# braids_v50.net
KiCad netlist of a schematic drawn in EAGLE
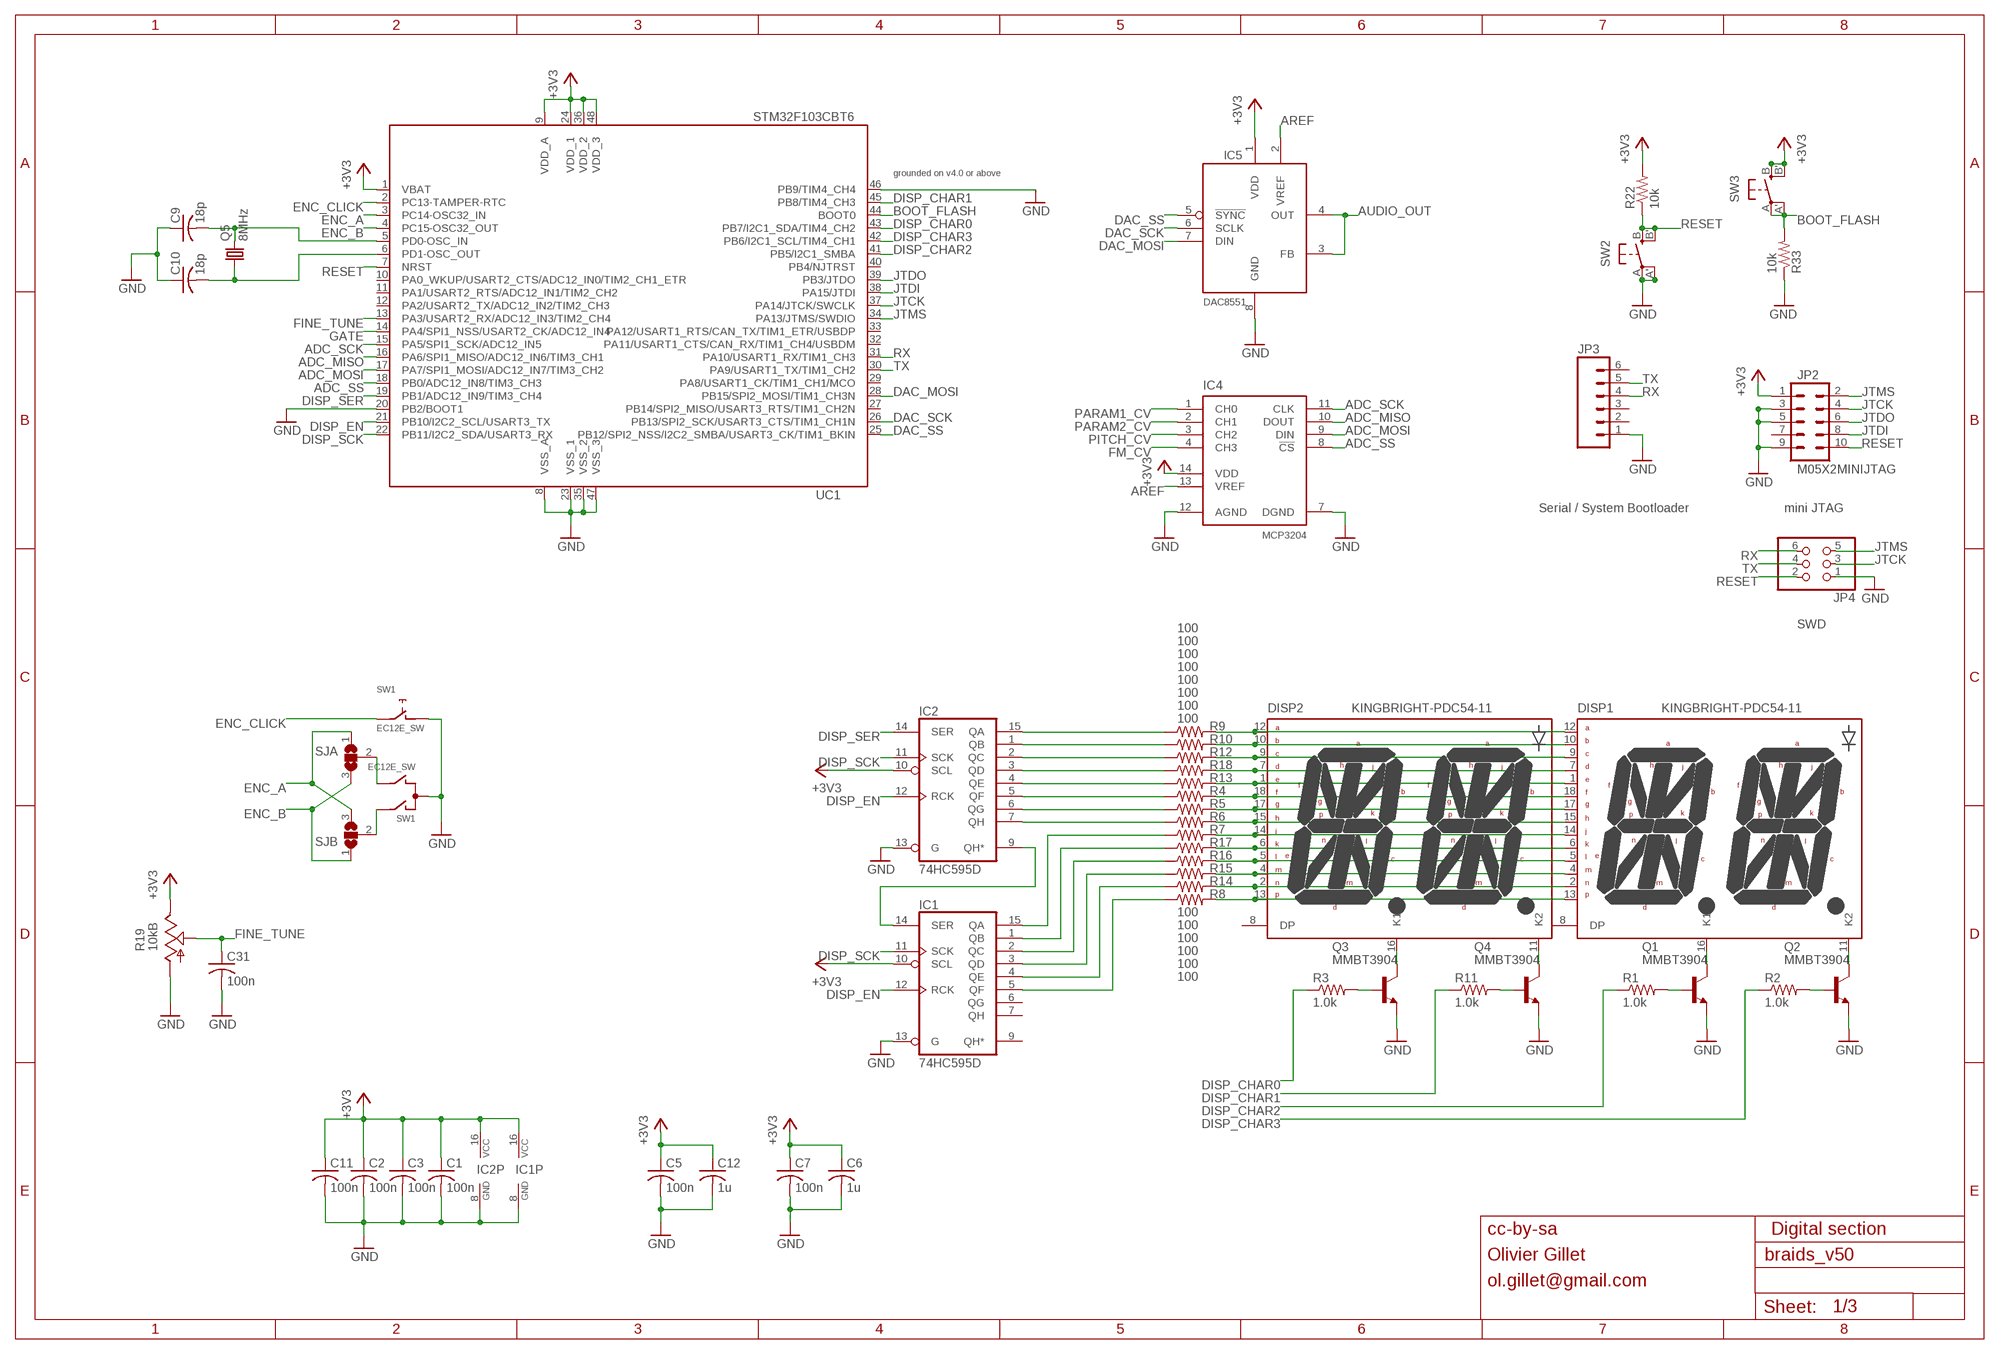
[diagram p0: schematic, sheet 1]
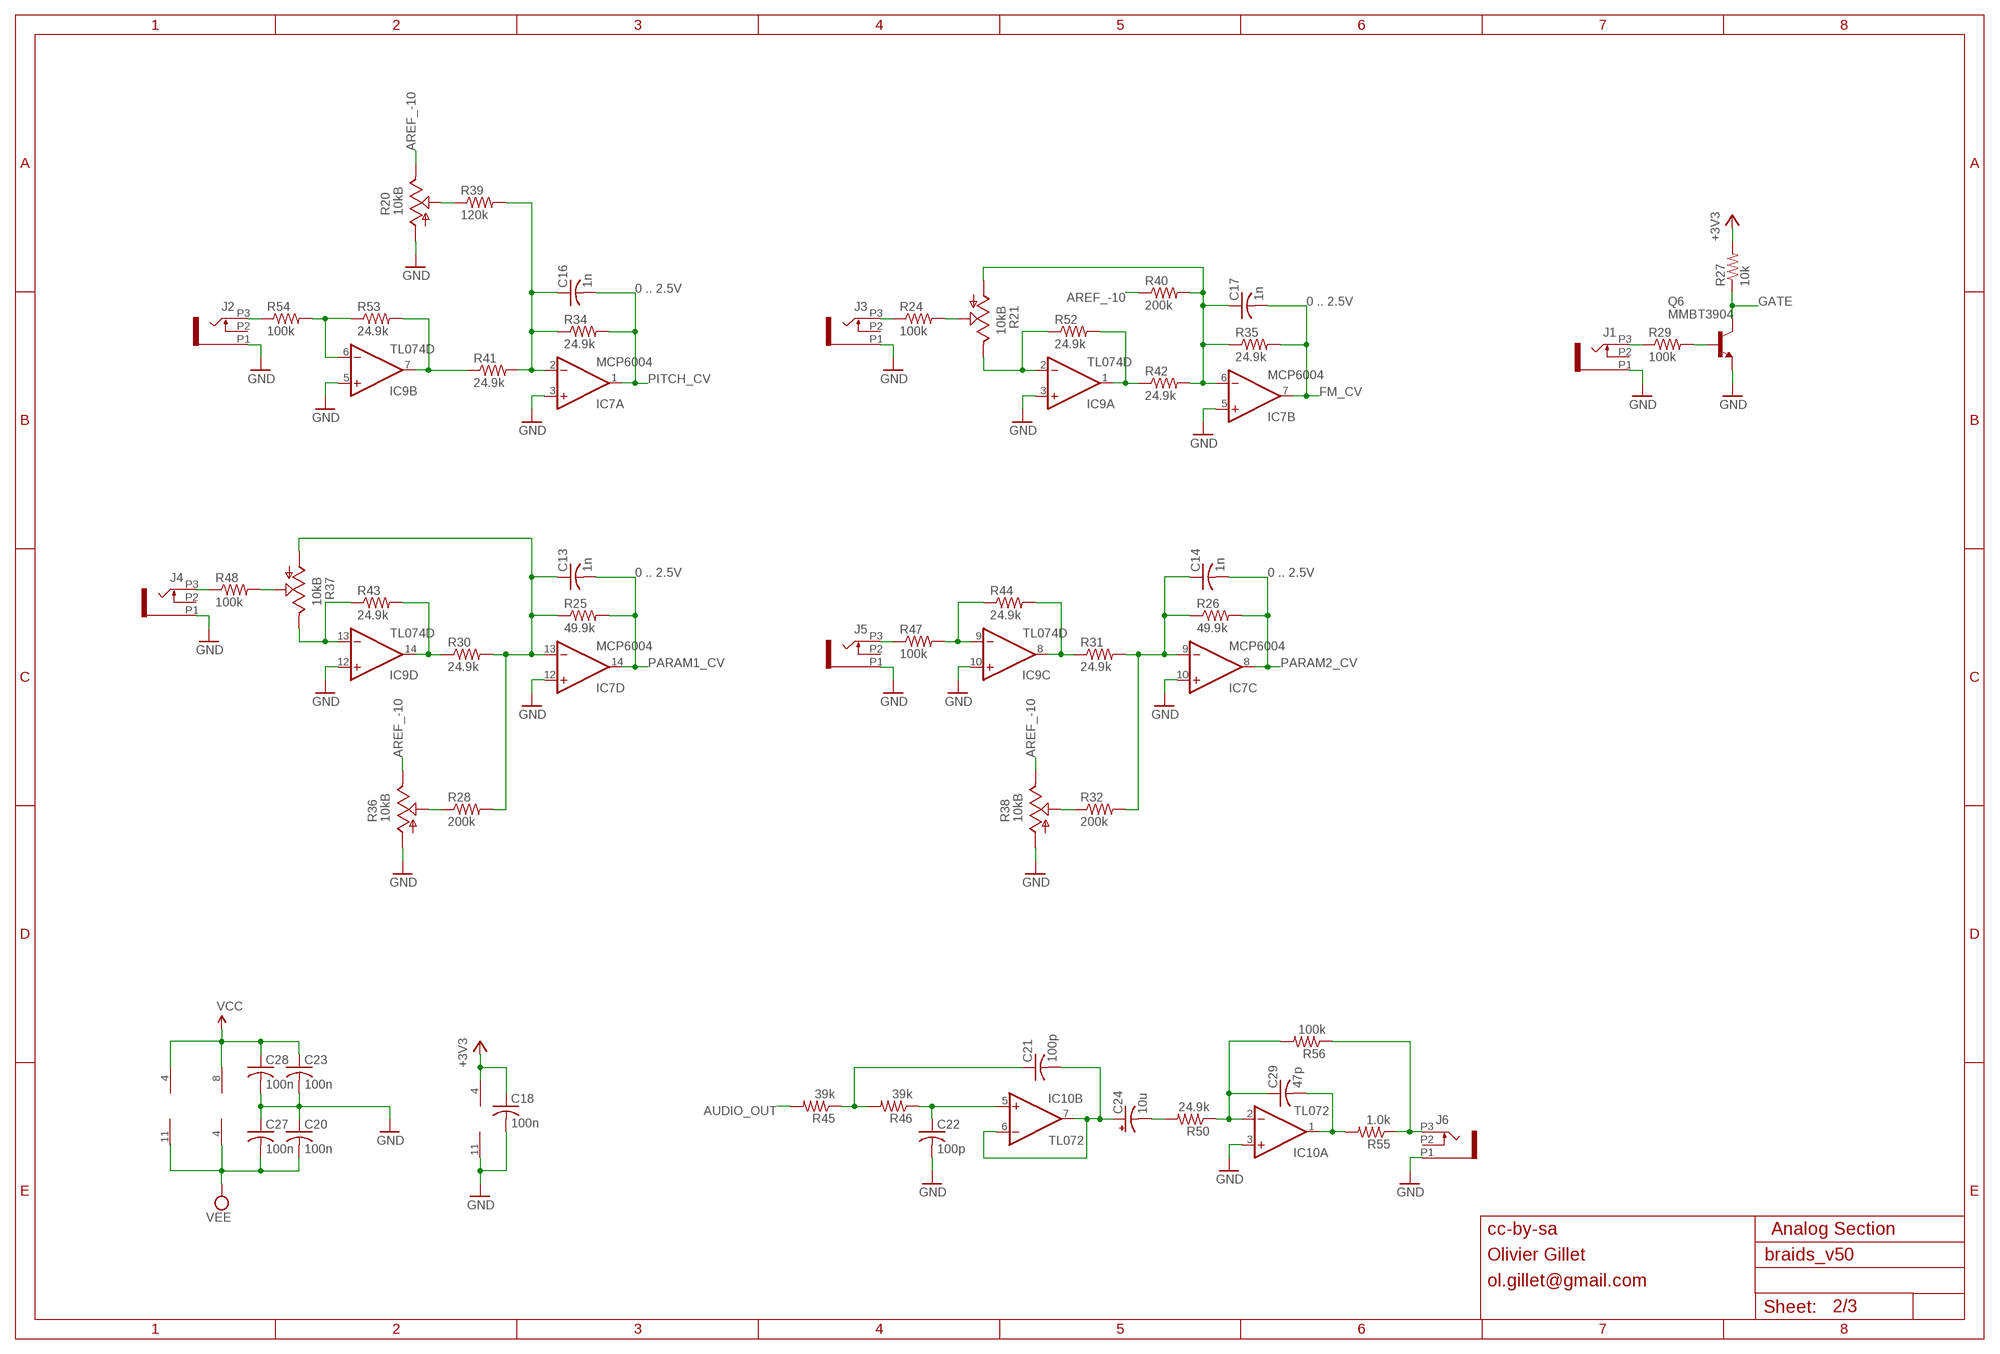
[diagram p1: schematic, sheet 2]
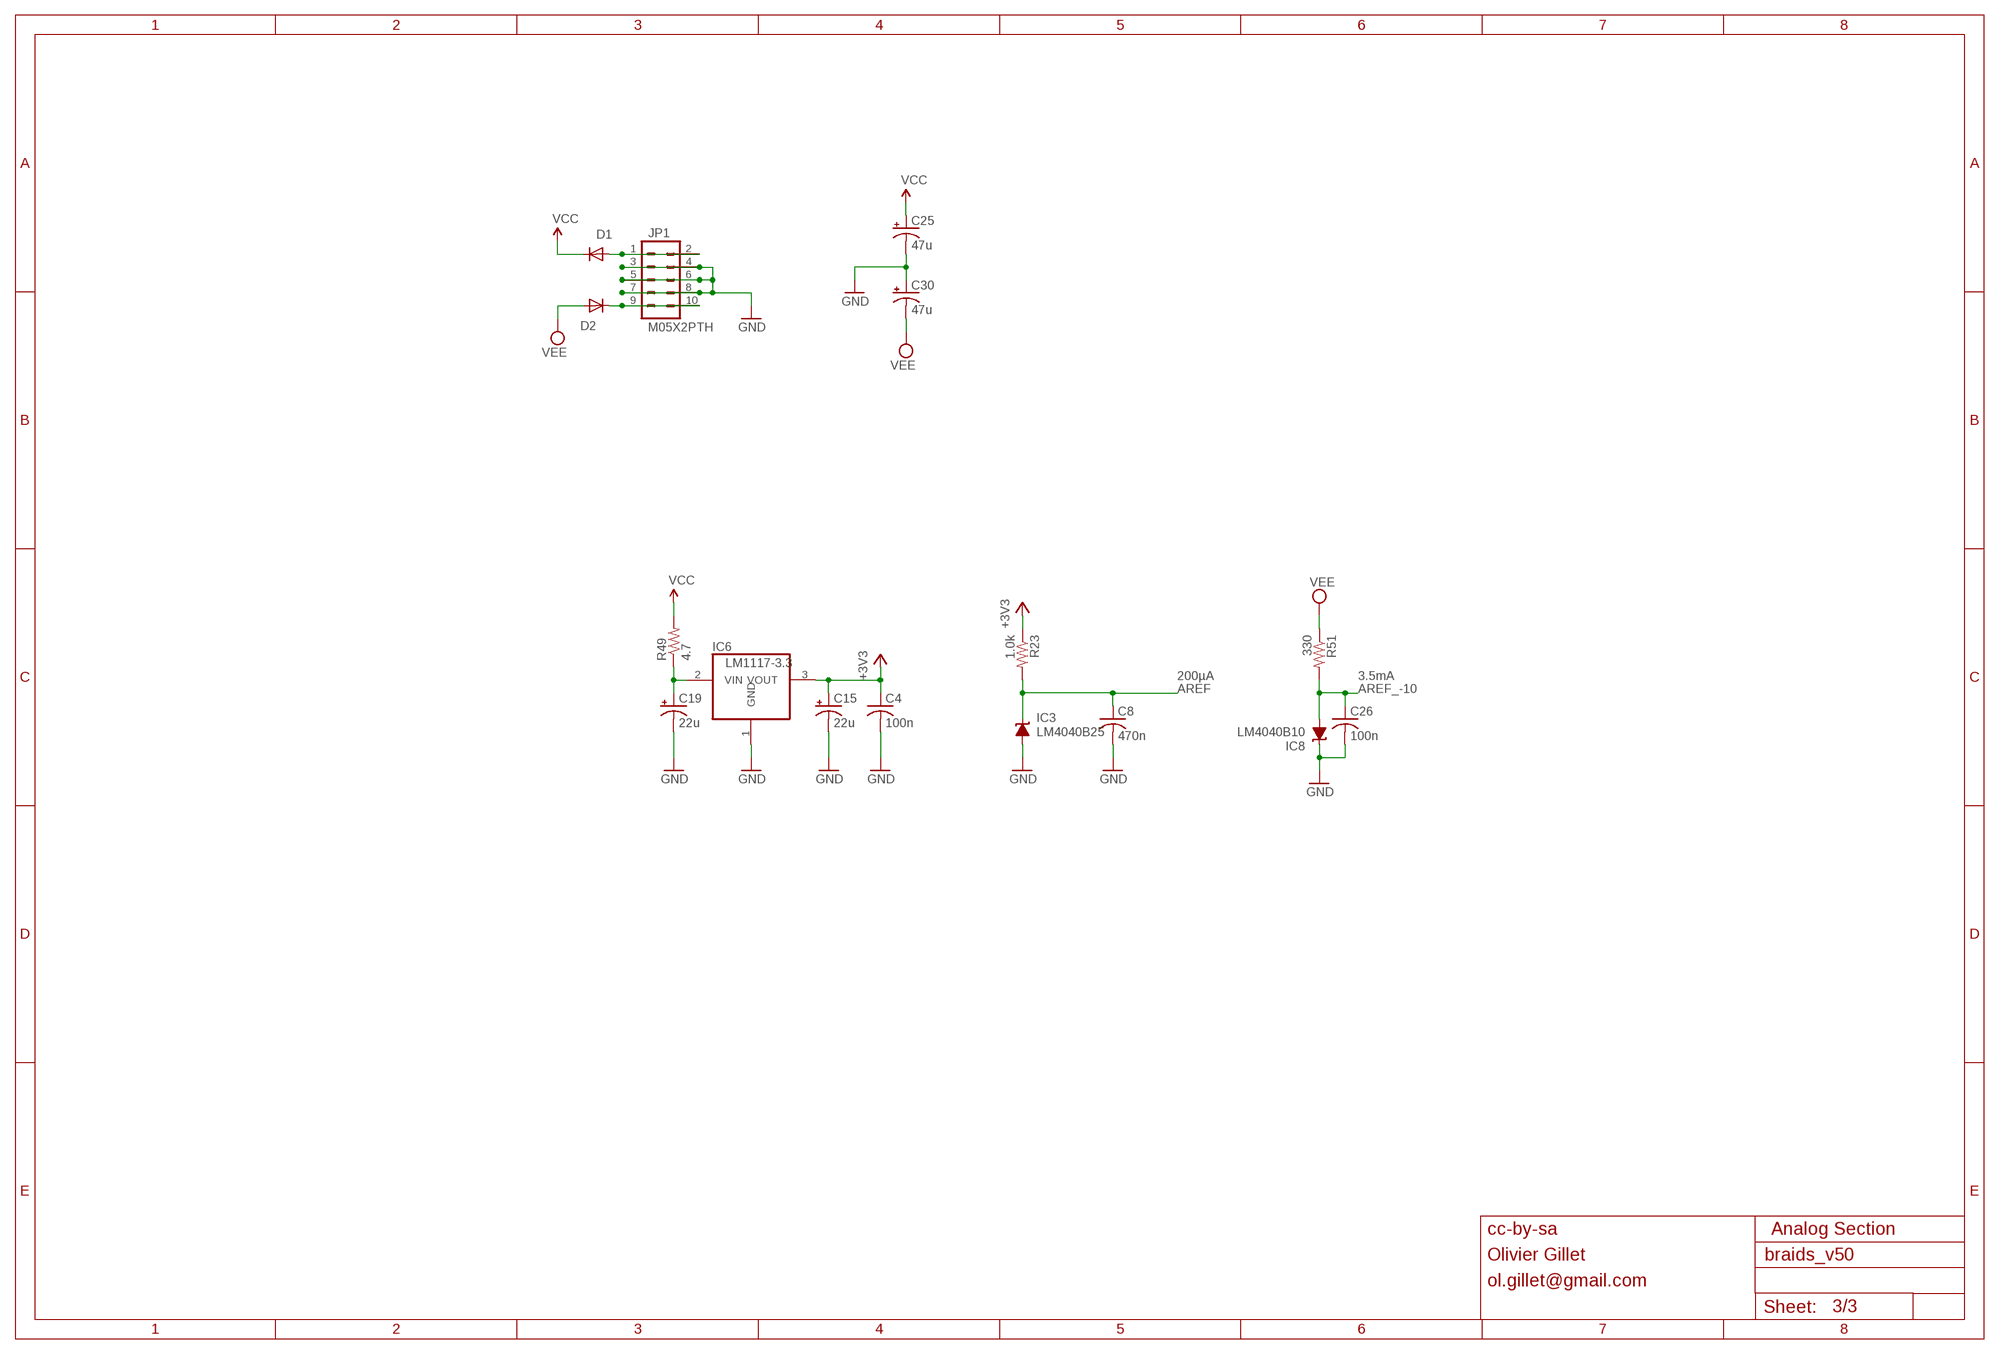
[diagram p2: schematic, sheet 3]

(export (version "E")
  (design (tool "Eeschema 10.0.6"))
  (components
    (comp (ref "C13")
      (value "1n")
      (footprint "eagle-import:C0603")
      (libsource (lib "eagle-import") (part "C-USC0603"))
    )
    (comp (ref "C14")
      (value "1n")
      (footprint "eagle-import:C0603")
      (libsource (lib "eagle-import") (part "C-USC0603"))
    )
    (comp (ref "C16")
      (value "1n")
      (footprint "eagle-import:C0603")
      (libsource (lib "eagle-import") (part "C-USC0603"))
    )
    (comp (ref "C17")
      (value "1n")
      (footprint "eagle-import:C0603")
      (libsource (lib "eagle-import") (part "C-USC0603"))
    )
    (comp (ref "C18")
      (value "100n")
      (footprint "eagle-import:C0603")
      (libsource (lib "eagle-import") (part "C-USC0603"))
    )
    (comp (ref "C20")
      (value "100n")
      (footprint "eagle-import:C0603")
      (libsource (lib "eagle-import") (part "C-USC0603"))
    )
    (comp (ref "C21")
      (value "100p")
      (footprint "eagle-import:C0603")
      (libsource (lib "eagle-import") (part "C-USC0603"))
    )
    (comp (ref "C22")
      (value "100p")
      (footprint "eagle-import:C0603")
      (libsource (lib "eagle-import") (part "C-USC0603"))
    )
    (comp (ref "C23")
      (value "100n")
      (footprint "eagle-import:C0603")
      (libsource (lib "eagle-import") (part "C-USC0603"))
    )
    (comp (ref "C24")
      (value "10u")
      (footprint "eagle-import:PANASONIC_B")
      (libsource (lib "eagle-import") (part "CPOL-USB"))
    )
    (comp (ref "C27")
      (value "100n")
      (footprint "eagle-import:C0603")
      (libsource (lib "eagle-import") (part "C-USC0603"))
    )
    (comp (ref "C28")
      (value "100n")
      (footprint "eagle-import:C0603")
      (libsource (lib "eagle-import") (part "C-USC0603"))
    )
    (comp (ref "C29")
      (value "47p")
      (footprint "eagle-import:C0603")
      (libsource (lib "eagle-import") (part "C-USC0603"))
    )
    (comp (ref "IC7")
      (value "MCP6004")
      (footprint "eagle-import:SO14")
      (libsource (lib "eagle-import") (part "TL074D"))
    )
    (comp (ref "IC9")
      (value "TL074D")
      (footprint "eagle-import:SO14")
      (libsource (lib "eagle-import") (part "TL074D"))
    )
    (comp (ref "IC10")
      (value "TL072")
      (footprint "eagle-import:SO08")
      (libsource (lib "eagle-import") (part "TL072D"))
    )
    (comp (ref "J1")
      (value "PJ301_THONKICONN6")
      (footprint "eagle-import:WQP_PJ_301M6")
      (libsource (lib "eagle-import") (part "PJ301_THONKICONN6"))
    )
    (comp (ref "J2")
      (value "PJ301_THONKICONN6")
      (footprint "eagle-import:WQP_PJ_301M6")
      (libsource (lib "eagle-import") (part "PJ301_THONKICONN6"))
    )
    (comp (ref "J3")
      (value "PJ301_THONKICONN6")
      (footprint "eagle-import:WQP_PJ_301M6")
      (libsource (lib "eagle-import") (part "PJ301_THONKICONN6"))
    )
    (comp (ref "J4")
      (value "PJ301_THONKICONN6")
      (footprint "eagle-import:WQP_PJ_301M6")
      (libsource (lib "eagle-import") (part "PJ301_THONKICONN6"))
    )
    (comp (ref "J5")
      (value "PJ301_THONKICONN6")
      (footprint "eagle-import:WQP_PJ_301M6")
      (libsource (lib "eagle-import") (part "PJ301_THONKICONN6"))
    )
    (comp (ref "J6")
      (value "PJ301_THONKICONN6")
      (footprint "eagle-import:WQP_PJ_301M6")
      (libsource (lib "eagle-import") (part "PJ301_THONKICONN6"))
    )
    (comp (ref "Q6")
      (value "MMBT3904")
      (footprint "eagle-import:SOT23-BEC")
      (libsource (lib "eagle-import") (part "-NPN-SOT23-BECMMBT3904LT1"))
    )
    (comp (ref "R20")
      (value "10kB")
      (footprint "eagle-import:ALPS_POT_VERTICAL_PS")
      (libsource (lib "eagle-import") (part "POT_USVERTICAL_PS"))
    )
    (comp (ref "R21")
      (value "10kB")
      (footprint "eagle-import:ALPS_POT_VERTICAL_PS")
      (libsource (lib "eagle-import") (part "POT_USVERTICAL_PS"))
    )
    (comp (ref "R24")
      (value "100k")
      (footprint "eagle-import:R0603")
      (libsource (lib "eagle-import") (part "R-US_R0603"))
    )
    (comp (ref "R25")
      (value "49.9k")
      (footprint "eagle-import:R0603")
      (libsource (lib "eagle-import") (part "R-US_R0603"))
    )
    (comp (ref "R26")
      (value "49.9k")
      (footprint "eagle-import:R0603")
      (libsource (lib "eagle-import") (part "R-US_R0603"))
    )
    (comp (ref "R27")
      (value "10k")
      (footprint "eagle-import:R0603")
      (libsource (lib "eagle-import") (part "R-US_R0603"))
    )
    (comp (ref "R28")
      (value "200k")
      (footprint "eagle-import:R0603")
      (libsource (lib "eagle-import") (part "R-US_R0603"))
    )
    (comp (ref "R29")
      (value "100k")
      (footprint "eagle-import:R0603")
      (libsource (lib "eagle-import") (part "R-US_R0603"))
    )
    (comp (ref "R30")
      (value "24.9k")
      (footprint "eagle-import:R0603")
      (libsource (lib "eagle-import") (part "R-US_R0603"))
    )
    (comp (ref "R31")
      (value "24.9k")
      (footprint "eagle-import:R0603")
      (libsource (lib "eagle-import") (part "R-US_R0603"))
    )
    (comp (ref "R32")
      (value "200k")
      (footprint "eagle-import:R0603")
      (libsource (lib "eagle-import") (part "R-US_R0603"))
    )
    (comp (ref "R34")
      (value "24.9k")
      (footprint "eagle-import:R0603")
      (libsource (lib "eagle-import") (part "R-US_R0603"))
    )
    (comp (ref "R35")
      (value "24.9k")
      (footprint "eagle-import:R0603")
      (libsource (lib "eagle-import") (part "R-US_R0603"))
    )
    (comp (ref "R36")
      (value "10kB")
      (footprint "eagle-import:ALPS_POT_VERTICAL_PS")
      (libsource (lib "eagle-import") (part "POT_USVERTICAL_PS"))
    )
    (comp (ref "R37")
      (value "10kB")
      (footprint "eagle-import:ALPS_POT_VERTICAL_PS")
      (libsource (lib "eagle-import") (part "POT_USVERTICAL_PS"))
    )
    (comp (ref "R38")
      (value "10kB")
      (footprint "eagle-import:ALPS_POT_VERTICAL_PS")
      (libsource (lib "eagle-import") (part "POT_USVERTICAL_PS"))
    )
    (comp (ref "R39")
      (value "120k")
      (footprint "eagle-import:R0603")
      (libsource (lib "eagle-import") (part "R-US_R0603"))
    )
    (comp (ref "R40")
      (value "200k")
      (footprint "eagle-import:R0603")
      (libsource (lib "eagle-import") (part "R-US_R0603"))
    )
    (comp (ref "R41")
      (value "24.9k")
      (footprint "eagle-import:R0603")
      (libsource (lib "eagle-import") (part "R-US_R0603"))
    )
    (comp (ref "R42")
      (value "24.9k")
      (footprint "eagle-import:R0603")
      (libsource (lib "eagle-import") (part "R-US_R0603"))
    )
    (comp (ref "R43")
      (value "24.9k")
      (footprint "eagle-import:R0603")
      (libsource (lib "eagle-import") (part "R-US_R0603"))
    )
    (comp (ref "R44")
      (value "24.9k")
      (footprint "eagle-import:R0603")
      (libsource (lib "eagle-import") (part "R-US_R0603"))
    )
    (comp (ref "R45")
      (value "39k")
      (footprint "eagle-import:R0603")
      (libsource (lib "eagle-import") (part "R-US_R0603"))
    )
    (comp (ref "R46")
      (value "39k")
      (footprint "eagle-import:R0603")
      (libsource (lib "eagle-import") (part "R-US_R0603"))
    )
    (comp (ref "R47")
      (value "100k")
      (footprint "eagle-import:R0603")
      (libsource (lib "eagle-import") (part "R-US_R0603"))
    )
    (comp (ref "R48")
      (value "100k")
      (footprint "eagle-import:R0603")
      (libsource (lib "eagle-import") (part "R-US_R0603"))
    )
    (comp (ref "R50")
      (value "24.9k")
      (footprint "eagle-import:R0603")
      (libsource (lib "eagle-import") (part "R-US_R0603"))
    )
    (comp (ref "R52")
      (value "24.9k")
      (footprint "eagle-import:R0603")
      (libsource (lib "eagle-import") (part "R-US_R0603"))
    )
    (comp (ref "R53")
      (value "24.9k")
      (footprint "eagle-import:R0603")
      (libsource (lib "eagle-import") (part "R-US_R0603"))
    )
    (comp (ref "R54")
      (value "100k")
      (footprint "eagle-import:R0603")
      (libsource (lib "eagle-import") (part "R-US_R0603"))
    )
    (comp (ref "R55")
      (value "1.0k")
      (footprint "eagle-import:R0603")
      (libsource (lib "eagle-import") (part "R-US_R0603"))
    )
    (comp (ref "R56")
      (value "100k")
      (footprint "eagle-import:R0603")
      (libsource (lib "eagle-import") (part "R-US_R0603"))
    )
    (comp (ref "C1")
      (value "100n")
      (footprint "eagle-import:C0603")
      (libsource (lib "eagle-import") (part "C-USC0603"))
    )
    (comp (ref "C2")
      (value "100n")
      (footprint "eagle-import:C0603")
      (libsource (lib "eagle-import") (part "C-USC0603"))
    )
    (comp (ref "C3")
      (value "100n")
      (footprint "eagle-import:C0603")
      (libsource (lib "eagle-import") (part "C-USC0603"))
    )
    (comp (ref "C5")
      (value "100n")
      (footprint "eagle-import:C0603")
      (libsource (lib "eagle-import") (part "C-USC0603"))
    )
    (comp (ref "C6")
      (value "1u")
      (footprint "eagle-import:C0603")
      (libsource (lib "eagle-import") (part "C-USC0603"))
    )
    (comp (ref "C7")
      (value "100n")
      (footprint "eagle-import:C0603")
      (libsource (lib "eagle-import") (part "C-USC0603"))
    )
    (comp (ref "C9")
      (value "18p")
      (footprint "eagle-import:C0603")
      (libsource (lib "eagle-import") (part "C-USC0603"))
    )
    (comp (ref "C10")
      (value "18p")
      (footprint "eagle-import:C0603")
      (libsource (lib "eagle-import") (part "C-USC0603"))
    )
    (comp (ref "C11")
      (value "100n")
      (footprint "eagle-import:C0603")
      (libsource (lib "eagle-import") (part "C-USC0603"))
    )
    (comp (ref "C12")
      (value "1u")
      (footprint "eagle-import:C0603")
      (libsource (lib "eagle-import") (part "C-USC0603"))
    )
    (comp (ref "C31")
      (value "100n")
      (footprint "eagle-import:C0603")
      (libsource (lib "eagle-import") (part "C-USC0603"))
    )
    (comp (ref "DISP1")
      (value "KINGBRIGHT-PDC54-11")
      (footprint "eagle-import:PDC54")
      (libsource (lib "eagle-import") (part "KINGBRIGHT-PDC54-11"))
    )
    (comp (ref "DISP2")
      (value "KINGBRIGHT-PDC54-11")
      (footprint "eagle-import:PDC54")
      (libsource (lib "eagle-import") (part "KINGBRIGHT-PDC54-11"))
    )
    (comp (ref "IC1")
      (value "74HC595D")
      (footprint "eagle-import:SO16")
      (libsource (lib "eagle-import") (part "74595DHC"))
    )
    (comp (ref "IC2")
      (value "74HC595D")
      (footprint "eagle-import:SO16")
      (libsource (lib "eagle-import") (part "74595DHC"))
    )
    (comp (ref "IC4")
      (value "MCP3204")
      (footprint "eagle-import:SO14")
      (libsource (lib "eagle-import") (part "MCP3302"))
    )
    (comp (ref "IC5")
      (value "DAC8551")
      (footprint "eagle-import:MSOP-8")
      (libsource (lib "eagle-import") (part "DAC855X"))
    )
    (comp (ref "JP2")
      (value "M05X2MINIJTAG")
      (footprint "eagle-import:2X5-1.27")
      (libsource (lib "eagle-import") (part "M05X2MINIJTAG"))
    )
    (comp (ref "JP3")
      (value "M06SIP")
      (footprint "eagle-import:1X06")
      (libsource (lib "eagle-import") (part "M06SIP"))
    )
    (comp (ref "JP4")
      (value "PINHD-2X3\"")
      (footprint "eagle-import:2X03")
      (libsource (lib "eagle-import") (part "PINHD-2X3{dblquote}"))
    )
    (comp (ref "Q1")
      (value "MMBT3904")
      (footprint "eagle-import:SOT23-BEC")
      (libsource (lib "eagle-import") (part "-NPN-SOT23-BECMMBT3904LT1"))
    )
    (comp (ref "Q2")
      (value "MMBT3904")
      (footprint "eagle-import:SOT23-BEC")
      (libsource (lib "eagle-import") (part "-NPN-SOT23-BECMMBT3904LT1"))
    )
    (comp (ref "Q3")
      (value "MMBT3904")
      (footprint "eagle-import:SOT23-BEC")
      (libsource (lib "eagle-import") (part "-NPN-SOT23-BECMMBT3904LT1"))
    )
    (comp (ref "Q4")
      (value "MMBT3904")
      (footprint "eagle-import:SOT23-BEC")
      (libsource (lib "eagle-import") (part "-NPN-SOT23-BECMMBT3904LT1"))
    )
    (comp (ref "Q5")
      (value "8MHz")
      (footprint "eagle-import:HC49UP")
      (libsource (lib "eagle-import") (part "CRYSTALHC49UP"))
    )
    (comp (ref "R1")
      (value "1.0k")
      (footprint "eagle-import:R0603")
      (libsource (lib "eagle-import") (part "R-US_R0603"))
    )
    (comp (ref "R2")
      (value "1.0k")
      (footprint "eagle-import:R0603")
      (libsource (lib "eagle-import") (part "R-US_R0603"))
    )
    (comp (ref "R3")
      (value "1.0k")
      (footprint "eagle-import:R0603")
      (libsource (lib "eagle-import") (part "R-US_R0603"))
    )
    (comp (ref "R4")
      (value "100")
      (footprint "eagle-import:R0603")
      (libsource (lib "eagle-import") (part "R-US_R0603"))
    )
    (comp (ref "R5")
      (value "100")
      (footprint "eagle-import:R0603")
      (libsource (lib "eagle-import") (part "R-US_R0603"))
    )
    (comp (ref "R6")
      (value "100")
      (footprint "eagle-import:R0603")
      (libsource (lib "eagle-import") (part "R-US_R0603"))
    )
    (comp (ref "R7")
      (value "100")
      (footprint "eagle-import:R0603")
      (libsource (lib "eagle-import") (part "R-US_R0603"))
    )
    (comp (ref "R8")
      (value "100")
      (footprint "eagle-import:R0603")
      (libsource (lib "eagle-import") (part "R-US_R0603"))
    )
    (comp (ref "R9")
      (value "100")
      (footprint "eagle-import:R0603")
      (libsource (lib "eagle-import") (part "R-US_R0603"))
    )
    (comp (ref "R10")
      (value "100")
      (footprint "eagle-import:R0603")
      (libsource (lib "eagle-import") (part "R-US_R0603"))
    )
    (comp (ref "R11")
      (value "1.0k")
      (footprint "eagle-import:R0603")
      (libsource (lib "eagle-import") (part "R-US_R0603"))
    )
    (comp (ref "R12")
      (value "100")
      (footprint "eagle-import:R0603")
      (libsource (lib "eagle-import") (part "R-US_R0603"))
    )
    (comp (ref "R13")
      (value "100")
      (footprint "eagle-import:R0603")
      (libsource (lib "eagle-import") (part "R-US_R0603"))
    )
    (comp (ref "R14")
      (value "100")
      (footprint "eagle-import:R0603")
      (libsource (lib "eagle-import") (part "R-US_R0603"))
    )
    (comp (ref "R15")
      (value "100")
      (footprint "eagle-import:R0603")
      (libsource (lib "eagle-import") (part "R-US_R0603"))
    )
    (comp (ref "R16")
      (value "100")
      (footprint "eagle-import:R0603")
      (libsource (lib "eagle-import") (part "R-US_R0603"))
    )
    (comp (ref "R17")
      (value "100")
      (footprint "eagle-import:R0603")
      (libsource (lib "eagle-import") (part "R-US_R0603"))
    )
    (comp (ref "R18")
      (value "100")
      (footprint "eagle-import:R0603")
      (libsource (lib "eagle-import") (part "R-US_R0603"))
    )
    (comp (ref "R19")
      (value "10kB")
      (footprint "eagle-import:ALPS_POT_VERTICAL_PS")
      (libsource (lib "eagle-import") (part "POT_USVERTICAL_PS"))
    )
    (comp (ref "R22")
      (value "10k")
      (footprint "eagle-import:R0603")
      (libsource (lib "eagle-import") (part "R-US_R0603"))
    )
    (comp (ref "R33")
      (value "10k")
      (footprint "eagle-import:R0603")
      (libsource (lib "eagle-import") (part "R-US_R0603"))
    )
    (comp (ref "SJA")
      (value "SJ2W")
      (footprint "eagle-import:SJ_2")
      (libsource (lib "eagle-import") (part "SJ2W"))
    )
    (comp (ref "SJB")
      (value "SJ2W")
      (footprint "eagle-import:SJ_2")
      (libsource (lib "eagle-import") (part "SJ2W"))
    )
    (comp (ref "SW1")
      (value "EC12E_SW")
      (footprint "eagle-import:ALPS_EC12E_SW")
      (libsource (lib "eagle-import") (part "EC12E_SW"))
    )
    (comp (ref "SW2")
      (value "EVQQ2")
      (footprint "eagle-import:EVQ-Q2")
      (libsource (lib "eagle-import") (part "EVQQ2"))
    )
    (comp (ref "SW3")
      (value "EVQQ2")
      (footprint "eagle-import:EVQ-Q2")
      (libsource (lib "eagle-import") (part "EVQQ2"))
    )
    (comp (ref "UC1")
      (value "STM32F103CBT6")
      (footprint "eagle-import:LQFP48")
      (libsource (lib "eagle-import") (part "STM32F103CB"))
    )
    (comp (ref "C4")
      (value "100n")
      (footprint "eagle-import:C0603")
      (libsource (lib "eagle-import") (part "C-USC0603"))
    )
    (comp (ref "C8")
      (value "470n")
      (footprint "eagle-import:C0603")
      (libsource (lib "eagle-import") (part "C-USC0603"))
    )
    (comp (ref "C15")
      (value "22u")
      (footprint "eagle-import:PANASONIC_C")
      (libsource (lib "eagle-import") (part "CPOL-USC"))
    )
    (comp (ref "C19")
      (value "22u")
      (footprint "eagle-import:PANASONIC_C")
      (libsource (lib "eagle-import") (part "CPOL-USC"))
    )
    (comp (ref "C25")
      (value "47u")
      (footprint "eagle-import:PANASONIC_D")
      (libsource (lib "eagle-import") (part "CPOL-USD"))
    )
    (comp (ref "C26")
      (value "100n")
      (footprint "eagle-import:C0603")
      (libsource (lib "eagle-import") (part "C-USC0603"))
    )
    (comp (ref "C30")
      (value "47u")
      (footprint "eagle-import:PANASONIC_D")
      (libsource (lib "eagle-import") (part "CPOL-USD"))
    )
    (comp (ref "D1")
      (value "1N5819HW")
      (footprint "eagle-import:SOD123")
      (libsource (lib "eagle-import") (part "DIODE-SOD123"))
    )
    (comp (ref "D2")
      (value "1N5819HW")
      (footprint "eagle-import:SOD123")
      (libsource (lib "eagle-import") (part "DIODE-SOD123"))
    )
    (comp (ref "IC3")
      (value "LM4040B25")
      (footprint "eagle-import:DBZ_R-PDSO-G3")
      (libsource (lib "eagle-import") (part "LM4041DBZB12"))
    )
    (comp (ref "IC6")
      (value "LM1117-3.3")
      (footprint "eagle-import:TO252")
      (libsource (lib "eagle-import") (part "REG1117T"))
    )
    (comp (ref "IC8")
      (value "LM4040B10")
      (footprint "eagle-import:DBZ_R-PDSO-G3")
      (libsource (lib "eagle-import") (part "LM4041DBZB12"))
    )
    (comp (ref "JP1")
      (value "M05X2PTH")
      (footprint "eagle-import:AVR_ICSP")
      (libsource (lib "eagle-import") (part "M05X2PTH"))
    )
    (comp (ref "R23")
      (value "1.0k")
      (footprint "eagle-import:R0603")
      (libsource (lib "eagle-import") (part "R-US_R0603"))
    )
    (comp (ref "R49")
      (value "4.7")
      (footprint "eagle-import:R1206")
      (libsource (lib "eagle-import") (part "R-US_R1206"))
    )
    (comp (ref "R51")
      (value "330")
      (footprint "eagle-import:R0603")
      (libsource (lib "eagle-import") (part "R-US_R0603"))
    )
  )
  (nets
    (net (code "1") (name "+3V3") (class "Default")
      (node (ref "C1") (pin "1") (pinfunction "1_1") (pintype "passive"))
      (node (ref "C11") (pin "1") (pinfunction "1_1") (pintype "passive"))
      (node (ref "C12") (pin "1") (pinfunction "1_1") (pintype "passive"))
      (node (ref "C15") (pin "+") (pinfunction "+_+") (pintype "passive"))
      (node (ref "C18") (pin "1") (pinfunction "1_1") (pintype "passive"))
      (node (ref "C2") (pin "1") (pinfunction "1_1") (pintype "passive"))
      (node (ref "C3") (pin "1") (pinfunction "1_1") (pintype "passive"))
      (node (ref "C4") (pin "1") (pinfunction "1_1") (pintype "passive"))
      (node (ref "C5") (pin "1") (pinfunction "1_1") (pintype "passive"))
      (node (ref "C6") (pin "1") (pinfunction "1_1") (pintype "passive"))
      (node (ref "C7") (pin "1") (pinfunction "1_1") (pintype "passive"))
      (node (ref "IC1") (pin "10") (pinfunction "SCL_10") (pintype "input"))
      (node (ref "IC1") (pin "16") (pinfunction "VCC_16") (pintype "power_in"))
      (node (ref "IC2") (pin "10") (pinfunction "SCL_10") (pintype "input"))
      (node (ref "IC2") (pin "16") (pinfunction "VCC_16") (pintype "power_in"))
      (node (ref "IC4") (pin "14") (pinfunction "VDD_14") (pintype "bidirectional"))
      (node (ref "IC5") (pin "1") (pinfunction "VDD_1") (pintype "power_in"))
      (node (ref "IC6") (pin "3") (pinfunction "VOUT_3") (pintype "output"))
      (node (ref "IC7") (pin "4") (pinfunction "V+_4") (pintype "power_in"))
      (node (ref "JP2") (pin "1") (pinfunction "1_1") (pintype "passive"))
      (node (ref "R19") (pin "P$1") (pinfunction "E_P$1") (pintype "passive"))
      (node (ref "R22") (pin "2") (pinfunction "2_2") (pintype "passive"))
      (node (ref "R23") (pin "1") (pinfunction "1_1") (pintype "passive"))
      (node (ref "R27") (pin "2") (pinfunction "2_2") (pintype "passive"))
      (node (ref "SW3") (pin "B") (pinfunction "S_B") (pintype "passive"))
      (node (ref "SW3") (pin "B'") (pinfunction "S1_B'") (pintype "passive"))
      (node (ref "UC1") (pin "1") (pinfunction "VBAT_1") (pintype "power_in"))
      (node (ref "UC1") (pin "24") (pinfunction "VDD_1_24") (pintype "power_in"))
      (node (ref "UC1") (pin "36") (pinfunction "VDD_2_36") (pintype "power_in"))
      (node (ref "UC1") (pin "48") (pinfunction "VDD_3_48") (pintype "power_in"))
      (node (ref "UC1") (pin "9") (pinfunction "VDD_A_9") (pintype "power_in"))
    )
    (net (code "2") (name "ADC_MISO") (class "Default")
      (node (ref "IC4") (pin "10") (pinfunction "DOUT_10") (pintype "bidirectional"))
      (node (ref "UC1") (pin "16") (pinfunction "PA6/SPI1_MISO/ADC12_IN6/TIM3_CH1_16") (pintype "bidirectional"))
    )
    (net (code "3") (name "ADC_MOSI") (class "Default")
      (node (ref "IC4") (pin "9") (pinfunction "DIN_9") (pintype "bidirectional"))
      (node (ref "UC1") (pin "17") (pinfunction "PA7/SPI1_MOSI/ADC12_IN7/TIM3_CH2_17") (pintype "bidirectional"))
    )
    (net (code "4") (name "ADC_SCK") (class "Default")
      (node (ref "IC4") (pin "11") (pinfunction "CLK_11") (pintype "bidirectional"))
      (node (ref "UC1") (pin "15") (pinfunction "PA5/SPI1_SCK/ADC12_IN5_15") (pintype "bidirectional"))
    )
    (net (code "5") (name "ADC_SS") (class "Default")
      (node (ref "IC4") (pin "8") (pinfunction "~{CS}_8") (pintype "bidirectional"))
      (node (ref "UC1") (pin "18") (pinfunction "PB0/ADC12_IN8/TIM3_CH3_18") (pintype "bidirectional"))
    )
    (net (code "6") (name "AREF") (class "Default")
      (node (ref "C8") (pin "1") (pinfunction "1_1") (pintype "passive"))
      (node (ref "IC3") (pin "1") (pinfunction "C_1") (pintype "passive"))
      (node (ref "IC4") (pin "13") (pinfunction "VREF_13") (pintype "bidirectional"))
      (node (ref "IC5") (pin "2") (pinfunction "VREF_2") (pintype "power_in"))
      (node (ref "R23") (pin "2") (pinfunction "2_2") (pintype "passive"))
    )
    (net (code "7") (name "AREF_-10") (class "Default")
      (node (ref "C26") (pin "1") (pinfunction "1_1") (pintype "passive"))
      (node (ref "IC8") (pin "2") (pinfunction "A_2") (pintype "passive"))
      (node (ref "R20") (pin "P$1") (pinfunction "E_P$1") (pintype "passive"))
      (node (ref "R36") (pin "P$1") (pinfunction "E_P$1") (pintype "passive"))
      (node (ref "R38") (pin "P$1") (pinfunction "E_P$1") (pintype "passive"))
      (node (ref "R40") (pin "1") (pinfunction "1_1") (pintype "passive"))
      (node (ref "R51") (pin "2") (pinfunction "2_2") (pintype "passive"))
    )
    (net (code "8") (name "AUDIO_OUT") (class "Default")
      (node (ref "IC5") (pin "3") (pinfunction "FB_3") (pintype "input"))
      (node (ref "IC5") (pin "4") (pinfunction "OUT_4") (pintype "output"))
      (node (ref "R45") (pin "2") (pinfunction "2_2") (pintype "passive"))
    )
    (net (code "9") (name "BOOT_FLASH") (class "Default")
      (node (ref "R33") (pin "2") (pinfunction "2_2") (pintype "passive"))
      (node (ref "SW3") (pin "A") (pinfunction "P_A") (pintype "passive"))
      (node (ref "SW3") (pin "A'") (pinfunction "P1_A'") (pintype "passive"))
      (node (ref "UC1") (pin "44") (pinfunction "BOOT0_44") (pintype "input"))
    )
    (net (code "10") (name "DAC_MOSI") (class "Default")
      (node (ref "IC5") (pin "7") (pinfunction "DIN_7") (pintype "bidirectional"))
      (node (ref "UC1") (pin "28") (pinfunction "PB15/SPI2_MOSI/TIM1_CH3N_28") (pintype "input"))
    )
    (net (code "11") (name "DAC_SCK") (class "Default")
      (node (ref "IC5") (pin "6") (pinfunction "SCLK_6") (pintype "bidirectional"))
      (node (ref "UC1") (pin "26") (pinfunction "PB13/SPI2_SCK/USART3_CTS/TIM1_CH1N_26") (pintype "input"))
    )
    (net (code "12") (name "DAC_SS") (class "Default")
      (node (ref "IC5") (pin "5") (pinfunction "~{SYNC}_5") (pintype "bidirectional"))
      (node (ref "UC1") (pin "25") (pinfunction "PB12/SPI2_NSS/I2C2_SMBA/USART3_CK/TIM1_BKIN_25") (pintype "input"))
    )
    (net (code "13") (name "DISP_CHAR0") (class "Default")
      (node (ref "R3") (pin "1") (pinfunction "1_1") (pintype "passive"))
      (node (ref "UC1") (pin "43") (pinfunction "PB7/I2C1_SDA/TIM4_CH2_43") (pintype "bidirectional"))
    )
    (net (code "14") (name "DISP_CHAR1") (class "Default")
      (node (ref "R11") (pin "1") (pinfunction "1_1") (pintype "passive"))
      (node (ref "UC1") (pin "45") (pinfunction "PB8/TIM4_CH3_45") (pintype "bidirectional"))
    )
    (net (code "15") (name "DISP_CHAR2") (class "Default")
      (node (ref "R1") (pin "1") (pinfunction "1_1") (pintype "passive"))
      (node (ref "UC1") (pin "41") (pinfunction "PB5/I2C1_SMBA_41") (pintype "input"))
    )
    (net (code "16") (name "DISP_CHAR3") (class "Default")
      (node (ref "R2") (pin "1") (pinfunction "1_1") (pintype "passive"))
      (node (ref "UC1") (pin "42") (pinfunction "PB6/I2C1_SCL/TIM4_CH1_42") (pintype "input"))
    )
    (net (code "17") (name "DISP_EN") (class "Default")
      (node (ref "IC1") (pin "12") (pinfunction "RCK_12") (pintype "input"))
      (node (ref "IC2") (pin "12") (pinfunction "RCK_12") (pintype "input"))
      (node (ref "UC1") (pin "21") (pinfunction "PB10/I2C2_SCL/USART3_TX_21") (pintype "input"))
    )
    (net (code "18") (name "DISP_SCK") (class "Default")
      (node (ref "IC1") (pin "11") (pinfunction "SCK_11") (pintype "input"))
      (node (ref "IC2") (pin "11") (pinfunction "SCK_11") (pintype "input"))
      (node (ref "UC1") (pin "22") (pinfunction "PB11/I2C2_SDA/USART3_RX_22") (pintype "input"))
    )
    (net (code "19") (name "DISP_SER") (class "Default")
      (node (ref "IC2") (pin "14") (pinfunction "SER_14") (pintype "input"))
      (node (ref "UC1") (pin "19") (pinfunction "PB1/ADC12_IN9/TIM3_CH4_19") (pintype "bidirectional"))
    )
    (net (code "20") (name "ENC_A") (class "Default")
      (node (ref "SJA") (pin "1") (pinfunction "1_1") (pintype "passive"))
      (node (ref "SJB") (pin "3") (pinfunction "3_3") (pintype "passive"))
      (node (ref "UC1") (pin "3") (pinfunction "PC14-OSC32_IN_3") (pintype "input"))
    )
    (net (code "21") (name "ENC_B") (class "Default")
      (node (ref "SJA") (pin "3") (pinfunction "3_3") (pintype "passive"))
      (node (ref "SJB") (pin "1") (pinfunction "1_1") (pintype "passive"))
      (node (ref "UC1") (pin "4") (pinfunction "PC15-OSC32_OUT_4") (pintype "input"))
    )
    (net (code "22") (name "ENC_CLICK") (class "Default")
      (node (ref "SW1") (pin "E") (pinfunction "2_E") (pintype "passive"))
      (node (ref "UC1") (pin "2") (pinfunction "PC13-TAMPER-RTC_2") (pintype "input"))
    )
    (net (code "23") (name "FINE_TUNE") (class "Default")
      (node (ref "C31") (pin "1") (pinfunction "1_1") (pintype "passive"))
      (node (ref "R19") (pin "P$2") (pinfunction "S_P$2") (pintype "passive"))
      (node (ref "UC1") (pin "13") (pinfunction "PA3/USART2_RX/ADC12_IN3/TIM2_CH4_13") (pintype "bidirectional"))
    )
    (net (code "24") (name "FM_CV") (class "Default")
      (node (ref "C17") (pin "2") (pinfunction "2_2") (pintype "passive"))
      (node (ref "IC4") (pin "4") (pinfunction "CH3_4") (pintype "bidirectional"))
      (node (ref "IC7") (pin "7") (pinfunction "OUT_7") (pintype "output"))
      (node (ref "R35") (pin "2") (pinfunction "2_2") (pintype "passive"))
    )
    (net (code "25") (name "GATE") (class "Default")
      (node (ref "Q6") (pin "C") (pinfunction "C_C") (pintype "passive"))
      (node (ref "R27") (pin "1") (pinfunction "1_1") (pintype "passive"))
      (node (ref "UC1") (pin "14") (pinfunction "PA4/SPI1_NSS/USART2_CK/ADC12_IN4_14") (pintype "bidirectional"))
    )
    (net (code "26") (name "GND") (class "Default")
      (node (ref "C1") (pin "2") (pinfunction "2_2") (pintype "passive"))
      (node (ref "C10") (pin "1") (pinfunction "1_1") (pintype "passive"))
      (node (ref "C11") (pin "2") (pinfunction "2_2") (pintype "passive"))
      (node (ref "C12") (pin "2") (pinfunction "2_2") (pintype "passive"))
      (node (ref "C15") (pin "-") (pinfunction "-_-") (pintype "passive"))
      (node (ref "C18") (pin "2") (pinfunction "2_2") (pintype "passive"))
      (node (ref "C19") (pin "-") (pinfunction "-_-") (pintype "passive"))
      (node (ref "C2") (pin "2") (pinfunction "2_2") (pintype "passive"))
      (node (ref "C20") (pin "1") (pinfunction "1_1") (pintype "passive"))
      (node (ref "C22") (pin "2") (pinfunction "2_2") (pintype "passive"))
      (node (ref "C23") (pin "2") (pinfunction "2_2") (pintype "passive"))
      (node (ref "C25") (pin "-") (pinfunction "-_-") (pintype "passive"))
      (node (ref "C26") (pin "2") (pinfunction "2_2") (pintype "passive"))
      (node (ref "C27") (pin "1") (pinfunction "1_1") (pintype "passive"))
      (node (ref "C28") (pin "2") (pinfunction "2_2") (pintype "passive"))
      (node (ref "C3") (pin "2") (pinfunction "2_2") (pintype "passive"))
      (node (ref "C30") (pin "+") (pinfunction "+_+") (pintype "passive"))
      (node (ref "C31") (pin "2") (pinfunction "2_2") (pintype "passive"))
      (node (ref "C4") (pin "2") (pinfunction "2_2") (pintype "passive"))
      (node (ref "C5") (pin "2") (pinfunction "2_2") (pintype "passive"))
      (node (ref "C6") (pin "2") (pinfunction "2_2") (pintype "passive"))
      (node (ref "C7") (pin "2") (pinfunction "2_2") (pintype "passive"))
      (node (ref "C8") (pin "2") (pinfunction "2_2") (pintype "passive"))
      (node (ref "C9") (pin "1") (pinfunction "1_1") (pintype "passive"))
      (node (ref "IC1") (pin "13") (pinfunction "G_13") (pintype "input"))
      (node (ref "IC1") (pin "8") (pinfunction "GND_8") (pintype "power_in"))
      (node (ref "IC10") (pin "3") (pinfunction "+IN_3") (pintype "input"))
      (node (ref "IC2") (pin "13") (pinfunction "G_13") (pintype "input"))
      (node (ref "IC2") (pin "8") (pinfunction "GND_8") (pintype "power_in"))
      (node (ref "IC3") (pin "2") (pinfunction "A_2") (pintype "passive"))
      (node (ref "IC4") (pin "12") (pinfunction "AGND_12") (pintype "bidirectional"))
      (node (ref "IC4") (pin "7") (pinfunction "DGND_7") (pintype "bidirectional"))
      (node (ref "IC5") (pin "8") (pinfunction "GND_8") (pintype "power_in"))
      (node (ref "IC6") (pin "1") (pinfunction "GND_1") (pintype "power_in"))
      (node (ref "IC7") (pin "10") (pinfunction "+IN_10") (pintype "input"))
      (node (ref "IC7") (pin "11") (pinfunction "V-_11") (pintype "power_in"))
      (node (ref "IC7") (pin "12") (pinfunction "+IN_12") (pintype "input"))
      (node (ref "IC7") (pin "3") (pinfunction "+IN_3") (pintype "input"))
      (node (ref "IC7") (pin "5") (pinfunction "+IN_5") (pintype "input"))
      (node (ref "IC8") (pin "1") (pinfunction "C_1") (pintype "passive"))
      (node (ref "IC9") (pin "10") (pinfunction "+IN_10") (pintype "input"))
      (node (ref "IC9") (pin "12") (pinfunction "+IN_12") (pintype "input"))
      (node (ref "IC9") (pin "3") (pinfunction "+IN_3") (pintype "input"))
      (node (ref "IC9") (pin "5") (pinfunction "+IN_5") (pintype "input"))
      (node (ref "J1") (pin "P1") (pinfunction "1_P1") (pintype "passive"))
      (node (ref "J2") (pin "P1") (pinfunction "1_P1") (pintype "passive"))
      (node (ref "J3") (pin "P1") (pinfunction "1_P1") (pintype "passive"))
      (node (ref "J4") (pin "P1") (pinfunction "1_P1") (pintype "passive"))
      (node (ref "J5") (pin "P1") (pinfunction "1_P1") (pintype "passive"))
      (node (ref "J6") (pin "P1") (pinfunction "1_P1") (pintype "passive"))
      (node (ref "JP1") (pin "3") (pinfunction "3_3") (pintype "passive"))
      (node (ref "JP1") (pin "4") (pinfunction "4_4") (pintype "passive"))
      (node (ref "JP1") (pin "5") (pinfunction "5_5") (pintype "passive"))
      (node (ref "JP1") (pin "6") (pinfunction "6_6") (pintype "passive"))
      (node (ref "JP1") (pin "7") (pinfunction "7_7") (pintype "passive"))
      (node (ref "JP1") (pin "8") (pinfunction "8_8") (pintype "passive"))
      (node (ref "JP2") (pin "3") (pinfunction "3_3") (pintype "passive"))
      (node (ref "JP2") (pin "5") (pinfunction "5_5") (pintype "passive"))
      (node (ref "JP2") (pin "9") (pinfunction "9_9") (pintype "passive"))
      (node (ref "JP3") (pin "1") (pinfunction "1_1") (pintype "passive"))
      (node (ref "JP4") (pin "1") (pinfunction "1_1") (pintype "passive"))
      (node (ref "Q1") (pin "E") (pinfunction "E_E") (pintype "passive"))
      (node (ref "Q2") (pin "E") (pinfunction "E_E") (pintype "passive"))
      (node (ref "Q3") (pin "E") (pinfunction "E_E") (pintype "passive"))
      (node (ref "Q4") (pin "E") (pinfunction "E_E") (pintype "passive"))
      (node (ref "Q6") (pin "E") (pinfunction "E_E") (pintype "passive"))
      (node (ref "R19") (pin "P$3") (pinfunction "A_P$3") (pintype "passive"))
      (node (ref "R20") (pin "P$3") (pinfunction "A_P$3") (pintype "passive"))
      (node (ref "R33") (pin "1") (pinfunction "1_1") (pintype "passive"))
      (node (ref "R36") (pin "P$3") (pinfunction "A_P$3") (pintype "passive"))
      (node (ref "R38") (pin "P$3") (pinfunction "A_P$3") (pintype "passive"))
      (node (ref "SW1") (pin "C") (pinfunction "C_C") (pintype "passive"))
      (node (ref "SW1") (pin "D") (pinfunction "1_D") (pintype "passive"))
      (node (ref "SW2") (pin "A") (pinfunction "P_A") (pintype "passive"))
      (node (ref "SW2") (pin "A'") (pinfunction "P1_A'") (pintype "passive"))
      (node (ref "UC1") (pin "20") (pinfunction "PB2/BOOT1_20") (pintype "bidirectional"))
      (node (ref "UC1") (pin "23") (pinfunction "VSS_1_23") (pintype "power_in"))
      (node (ref "UC1") (pin "35") (pinfunction "VSS_2_35") (pintype "power_in"))
      (node (ref "UC1") (pin "46") (pinfunction "PB9/TIM4_CH4_46") (pintype "input"))
      (node (ref "UC1") (pin "47") (pinfunction "VSS_3_47") (pintype "power_in"))
      (node (ref "UC1") (pin "8") (pinfunction "VSS_A_8") (pintype "power_in"))
    )
    (net (code "27") (name "JTCK") (class "Default")
      (node (ref "JP2") (pin "4") (pinfunction "4_4") (pintype "passive"))
      (node (ref "JP4") (pin "3") (pinfunction "3_3") (pintype "passive"))
      (node (ref "UC1") (pin "37") (pinfunction "PA14/JTCK/SWCLK_37") (pintype "bidirectional"))
    )
    (net (code "28") (name "JTDI") (class "Default")
      (node (ref "JP2") (pin "8") (pinfunction "8_8") (pintype "passive"))
      (node (ref "UC1") (pin "38") (pinfunction "PA15/JTDI_38") (pintype "bidirectional"))
    )
    (net (code "29") (name "JTDO") (class "Default")
      (node (ref "JP2") (pin "6") (pinfunction "6_6") (pintype "passive"))
      (node (ref "UC1") (pin "39") (pinfunction "PB3/JTDO_39") (pintype "bidirectional"))
    )
    (net (code "30") (name "JTMS") (class "Default")
      (node (ref "JP2") (pin "2") (pinfunction "2_2") (pintype "passive"))
      (node (ref "JP4") (pin "5") (pinfunction "5_5") (pintype "passive"))
      (node (ref "UC1") (pin "34") (pinfunction "PA13/JTMS/SWDIO_34") (pintype "bidirectional"))
    )
    (net (code "31") (name "Net-(C21-Pad1)") (class "Default")
      (node (ref "C21") (pin "1") (pinfunction "1_1") (pintype "passive"))
      (node (ref "R45") (pin "1") (pinfunction "1_1") (pintype "passive"))
      (node (ref "R46") (pin "2") (pinfunction "2_2") (pintype "passive"))
    )
    (net (code "32") (name "Net-(C24-Pad-)") (class "Default")
      (node (ref "C24") (pin "-") (pinfunction "-_-") (pintype "passive"))
      (node (ref "R50") (pin "2") (pinfunction "2_2") (pintype "passive"))
    )
    (net (code "33") (name "Net-(D1-PadA)") (class "Default")
      (node (ref "D1") (pin "A") (pinfunction "A_A") (pintype "passive"))
      (node (ref "JP1") (pin "1") (pinfunction "1_1") (pintype "passive"))
      (node (ref "JP1") (pin "2") (pinfunction "2_2") (pintype "passive"))
    )
    (net (code "34") (name "Net-(D2-PadC)") (class "Default")
      (node (ref "D2") (pin "C") (pinfunction "C_C") (pintype "passive"))
      (node (ref "JP1") (pin "10") (pinfunction "10_10") (pintype "passive"))
      (node (ref "JP1") (pin "9") (pinfunction "9_9") (pintype "passive"))
    )
    (net (code "35") (name "Net-(DISP1-A)") (class "Default")
      (node (ref "DISP1") (pin "12") (pinfunction "A_12") (pintype "passive"))
      (node (ref "DISP2") (pin "12") (pinfunction "A_12") (pintype "passive"))
      (node (ref "R9") (pin "2") (pinfunction "2_2") (pintype "passive"))
    )
    (net (code "36") (name "Net-(DISP1-B)") (class "Default")
      (node (ref "DISP1") (pin "10") (pinfunction "B_10") (pintype "passive"))
      (node (ref "DISP2") (pin "10") (pinfunction "B_10") (pintype "passive"))
      (node (ref "R10") (pin "2") (pinfunction "2_2") (pintype "passive"))
    )
    (net (code "37") (name "Net-(DISP1-C)") (class "Default")
      (node (ref "DISP1") (pin "9") (pinfunction "C_9") (pintype "passive"))
      (node (ref "DISP2") (pin "9") (pinfunction "C_9") (pintype "passive"))
      (node (ref "R12") (pin "2") (pinfunction "2_2") (pintype "passive"))
    )
    (net (code "38") (name "Net-(DISP1-D)") (class "Default")
      (node (ref "DISP1") (pin "7") (pinfunction "D_7") (pintype "passive"))
      (node (ref "DISP2") (pin "7") (pinfunction "D_7") (pintype "passive"))
      (node (ref "R18") (pin "2") (pinfunction "2_2") (pintype "passive"))
    )
    (net (code "39") (name "Net-(DISP1-E)") (class "Default")
      (node (ref "DISP1") (pin "1") (pinfunction "E_1") (pintype "passive"))
      (node (ref "DISP2") (pin "1") (pinfunction "E_1") (pintype "passive"))
      (node (ref "R13") (pin "2") (pinfunction "2_2") (pintype "passive"))
    )
    (net (code "40") (name "Net-(DISP1-F)") (class "Default")
      (node (ref "DISP1") (pin "18") (pinfunction "F_18") (pintype "passive"))
      (node (ref "DISP2") (pin "18") (pinfunction "F_18") (pintype "passive"))
      (node (ref "R4") (pin "2") (pinfunction "2_2") (pintype "passive"))
    )
    (net (code "41") (name "Net-(DISP1-G)") (class "Default")
      (node (ref "DISP1") (pin "17") (pinfunction "G_17") (pintype "passive"))
      (node (ref "DISP2") (pin "17") (pinfunction "G_17") (pintype "passive"))
      (node (ref "R5") (pin "2") (pinfunction "2_2") (pintype "passive"))
    )
    (net (code "42") (name "Net-(DISP1-H)") (class "Default")
      (node (ref "DISP1") (pin "15") (pinfunction "H_15") (pintype "passive"))
      (node (ref "DISP2") (pin "15") (pinfunction "H_15") (pintype "passive"))
      (node (ref "R6") (pin "2") (pinfunction "2_2") (pintype "passive"))
    )
    (net (code "43") (name "Net-(DISP1-J)") (class "Default")
      (node (ref "DISP1") (pin "14") (pinfunction "J_14") (pintype "passive"))
      (node (ref "DISP2") (pin "14") (pinfunction "J_14") (pintype "passive"))
      (node (ref "R7") (pin "2") (pinfunction "2_2") (pintype "passive"))
    )
    (net (code "44") (name "Net-(DISP1-K)") (class "Default")
      (node (ref "DISP1") (pin "6") (pinfunction "K_6") (pintype "passive"))
      (node (ref "DISP2") (pin "6") (pinfunction "K_6") (pintype "passive"))
      (node (ref "R17") (pin "2") (pinfunction "2_2") (pintype "passive"))
    )
    (net (code "45") (name "Net-(DISP1-K1)") (class "Default")
      (node (ref "DISP1") (pin "16") (pinfunction "K1_16") (pintype "passive"))
      (node (ref "Q1") (pin "C") (pinfunction "C_C") (pintype "passive"))
    )
    (net (code "46") (name "Net-(DISP1-K2)") (class "Default")
      (node (ref "DISP1") (pin "11") (pinfunction "K2_11") (pintype "passive"))
      (node (ref "Q2") (pin "C") (pinfunction "C_C") (pintype "passive"))
    )
    (net (code "47") (name "Net-(DISP1-L)") (class "Default")
      (node (ref "DISP1") (pin "5") (pinfunction "L_5") (pintype "passive"))
      (node (ref "DISP2") (pin "5") (pinfunction "L_5") (pintype "passive"))
      (node (ref "R16") (pin "2") (pinfunction "2_2") (pintype "passive"))
    )
    (net (code "48") (name "Net-(DISP1-M)") (class "Default")
      (node (ref "DISP1") (pin "4") (pinfunction "M_4") (pintype "passive"))
      (node (ref "DISP2") (pin "4") (pinfunction "M_4") (pintype "passive"))
      (node (ref "R15") (pin "2") (pinfunction "2_2") (pintype "passive"))
    )
    (net (code "49") (name "Net-(DISP1-N)") (class "Default")
      (node (ref "DISP1") (pin "2") (pinfunction "N_2") (pintype "passive"))
      (node (ref "DISP2") (pin "2") (pinfunction "N_2") (pintype "passive"))
      (node (ref "R14") (pin "2") (pinfunction "2_2") (pintype "passive"))
    )
    (net (code "50") (name "Net-(DISP1-P)") (class "Default")
      (node (ref "DISP1") (pin "13") (pinfunction "P_13") (pintype "passive"))
      (node (ref "DISP2") (pin "13") (pinfunction "P_13") (pintype "passive"))
      (node (ref "R8") (pin "2") (pinfunction "2_2") (pintype "passive"))
    )
    (net (code "51") (name "Net-(DISP2-K1)") (class "Default")
      (node (ref "DISP2") (pin "16") (pinfunction "K1_16") (pintype "passive"))
      (node (ref "Q3") (pin "C") (pinfunction "C_C") (pintype "passive"))
    )
    (net (code "52") (name "Net-(DISP2-K2)") (class "Default")
      (node (ref "DISP2") (pin "11") (pinfunction "K2_11") (pintype "passive"))
      (node (ref "Q4") (pin "C") (pinfunction "C_C") (pintype "passive"))
    )
    (net (code "53") (name "Net-(IC1A-QA)") (class "Default")
      (node (ref "IC1") (pin "15") (pinfunction "QA_15") (pintype "tri_state"))
      (node (ref "R7") (pin "1") (pinfunction "1_1") (pintype "passive"))
    )
    (net (code "54") (name "Net-(IC1A-QB)") (class "Default")
      (node (ref "IC1") (pin "1") (pinfunction "QB_1") (pintype "tri_state"))
      (node (ref "R17") (pin "1") (pinfunction "1_1") (pintype "passive"))
    )
    (net (code "55") (name "Net-(IC1A-QC)") (class "Default")
      (node (ref "IC1") (pin "2") (pinfunction "QC_2") (pintype "tri_state"))
      (node (ref "R16") (pin "1") (pinfunction "1_1") (pintype "passive"))
    )
    (net (code "56") (name "Net-(IC1A-QD)") (class "Default")
      (node (ref "IC1") (pin "3") (pinfunction "QD_3") (pintype "tri_state"))
      (node (ref "R15") (pin "1") (pinfunction "1_1") (pintype "passive"))
    )
    (net (code "57") (name "Net-(IC1A-QE)") (class "Default")
      (node (ref "IC1") (pin "4") (pinfunction "QE_4") (pintype "tri_state"))
      (node (ref "R14") (pin "1") (pinfunction "1_1") (pintype "passive"))
    )
    (net (code "58") (name "Net-(IC1A-QF)") (class "Default")
      (node (ref "IC1") (pin "5") (pinfunction "QF_5") (pintype "tri_state"))
      (node (ref "R8") (pin "1") (pinfunction "1_1") (pintype "passive"))
    )
    (net (code "59") (name "Net-(IC1A-SER)") (class "Default")
      (node (ref "IC1") (pin "14") (pinfunction "SER_14") (pintype "input"))
      (node (ref "IC2") (pin "9") (pinfunction "QH*_9") (pintype "tri_state"))
    )
    (net (code "60") (name "Net-(IC2A-QA)") (class "Default")
      (node (ref "IC2") (pin "15") (pinfunction "QA_15") (pintype "tri_state"))
      (node (ref "R9") (pin "1") (pinfunction "1_1") (pintype "passive"))
    )
    (net (code "61") (name "Net-(IC2A-QB)") (class "Default")
      (node (ref "IC2") (pin "1") (pinfunction "QB_1") (pintype "tri_state"))
      (node (ref "R10") (pin "1") (pinfunction "1_1") (pintype "passive"))
    )
    (net (code "62") (name "Net-(IC2A-QC)") (class "Default")
      (node (ref "IC2") (pin "2") (pinfunction "QC_2") (pintype "tri_state"))
      (node (ref "R12") (pin "1") (pinfunction "1_1") (pintype "passive"))
    )
    (net (code "63") (name "Net-(IC2A-QD)") (class "Default")
      (node (ref "IC2") (pin "3") (pinfunction "QD_3") (pintype "tri_state"))
      (node (ref "R18") (pin "1") (pinfunction "1_1") (pintype "passive"))
    )
    (net (code "64") (name "Net-(IC2A-QE)") (class "Default")
      (node (ref "IC2") (pin "4") (pinfunction "QE_4") (pintype "tri_state"))
      (node (ref "R13") (pin "1") (pinfunction "1_1") (pintype "passive"))
    )
    (net (code "65") (name "Net-(IC2A-QF)") (class "Default")
      (node (ref "IC2") (pin "5") (pinfunction "QF_5") (pintype "tri_state"))
      (node (ref "R4") (pin "1") (pinfunction "1_1") (pintype "passive"))
    )
    (net (code "66") (name "Net-(IC2A-QG)") (class "Default")
      (node (ref "IC2") (pin "6") (pinfunction "QG_6") (pintype "tri_state"))
      (node (ref "R5") (pin "1") (pinfunction "1_1") (pintype "passive"))
    )
    (net (code "67") (name "Net-(IC2A-QH)") (class "Default")
      (node (ref "IC2") (pin "7") (pinfunction "QH_7") (pintype "tri_state"))
      (node (ref "R6") (pin "1") (pinfunction "1_1") (pintype "passive"))
    )
    (net (code "68") (name "Net-(IC6-VIN)") (class "Default")
      (node (ref "C19") (pin "+") (pinfunction "+_+") (pintype "passive"))
      (node (ref "IC6") (pin "2") (pinfunction "VIN_2") (pintype "input"))
      (node (ref "R49") (pin "1") (pinfunction "1_1") (pintype "passive"))
    )
    (net (code "69") (name "Net-(IC7A--IN)") (class "Default")
      (node (ref "C16") (pin "1") (pinfunction "1_1") (pintype "passive"))
      (node (ref "IC7") (pin "2") (pinfunction "-IN_2") (pintype "input"))
      (node (ref "R34") (pin "1") (pinfunction "1_1") (pintype "passive"))
      (node (ref "R39") (pin "2") (pinfunction "2_2") (pintype "passive"))
      (node (ref "R41") (pin "2") (pinfunction "2_2") (pintype "passive"))
    )
    (net (code "70") (name "Net-(IC7B--IN)") (class "Default")
      (node (ref "C17") (pin "1") (pinfunction "1_1") (pintype "passive"))
      (node (ref "IC7") (pin "6") (pinfunction "-IN_6") (pintype "input"))
      (node (ref "R21") (pin "P$3") (pinfunction "A_P$3") (pintype "passive"))
      (node (ref "R35") (pin "1") (pinfunction "1_1") (pintype "passive"))
      (node (ref "R40") (pin "2") (pinfunction "2_2") (pintype "passive"))
      (node (ref "R42") (pin "2") (pinfunction "2_2") (pintype "passive"))
    )
    (net (code "71") (name "Net-(IC7C--IN)") (class "Default")
      (node (ref "C14") (pin "1") (pinfunction "1_1") (pintype "passive"))
      (node (ref "IC7") (pin "9") (pinfunction "-IN_9") (pintype "input"))
      (node (ref "R26") (pin "1") (pinfunction "1_1") (pintype "passive"))
      (node (ref "R31") (pin "2") (pinfunction "2_2") (pintype "passive"))
      (node (ref "R32") (pin "2") (pinfunction "2_2") (pintype "passive"))
    )
    (net (code "72") (name "Net-(IC7D--IN)") (class "Default")
      (node (ref "C13") (pin "1") (pinfunction "1_1") (pintype "passive"))
      (node (ref "IC7") (pin "13") (pinfunction "-IN_13") (pintype "input"))
      (node (ref "R25") (pin "1") (pinfunction "1_1") (pintype "passive"))
      (node (ref "R28") (pin "2") (pinfunction "2_2") (pintype "passive"))
      (node (ref "R30") (pin "2") (pinfunction "2_2") (pintype "passive"))
      (node (ref "R37") (pin "P$3") (pinfunction "A_P$3") (pintype "passive"))
    )
    (net (code "73") (name "Net-(IC9A--IN)") (class "Default")
      (node (ref "IC9") (pin "2") (pinfunction "-IN_2") (pintype "input"))
      (node (ref "R21") (pin "P$1") (pinfunction "E_P$1") (pintype "passive"))
      (node (ref "R52") (pin "1") (pinfunction "1_1") (pintype "passive"))
    )
    (net (code "74") (name "Net-(IC9A-OUT)") (class "Default")
      (node (ref "IC9") (pin "1") (pinfunction "OUT_1") (pintype "output"))
      (node (ref "R42") (pin "1") (pinfunction "1_1") (pintype "passive"))
      (node (ref "R52") (pin "2") (pinfunction "2_2") (pintype "passive"))
    )
    (net (code "75") (name "Net-(IC9B--IN)") (class "Default")
      (node (ref "IC9") (pin "6") (pinfunction "-IN_6") (pintype "input"))
      (node (ref "R53") (pin "1") (pinfunction "1_1") (pintype "passive"))
      (node (ref "R54") (pin "2") (pinfunction "2_2") (pintype "passive"))
    )
    (net (code "76") (name "Net-(IC9B-OUT)") (class "Default")
      (node (ref "IC9") (pin "7") (pinfunction "OUT_7") (pintype "output"))
      (node (ref "R41") (pin "1") (pinfunction "1_1") (pintype "passive"))
      (node (ref "R53") (pin "2") (pinfunction "2_2") (pintype "passive"))
    )
    (net (code "77") (name "Net-(IC9C--IN)") (class "Default")
      (node (ref "IC9") (pin "9") (pinfunction "-IN_9") (pintype "input"))
      (node (ref "R44") (pin "1") (pinfunction "1_1") (pintype "passive"))
      (node (ref "R47") (pin "2") (pinfunction "2_2") (pintype "passive"))
    )
    (net (code "78") (name "Net-(IC9C-OUT)") (class "Default")
      (node (ref "IC9") (pin "8") (pinfunction "OUT_8") (pintype "output"))
      (node (ref "R31") (pin "1") (pinfunction "1_1") (pintype "passive"))
      (node (ref "R44") (pin "2") (pinfunction "2_2") (pintype "passive"))
    )
    (net (code "79") (name "Net-(IC9D--IN)") (class "Default")
      (node (ref "IC9") (pin "13") (pinfunction "-IN_13") (pintype "input"))
      (node (ref "R37") (pin "P$1") (pinfunction "E_P$1") (pintype "passive"))
      (node (ref "R43") (pin "1") (pinfunction "1_1") (pintype "passive"))
    )
    (net (code "80") (name "Net-(IC9D-OUT)") (class "Default")
      (node (ref "IC9") (pin "14") (pinfunction "OUT_14") (pintype "output"))
      (node (ref "R30") (pin "1") (pinfunction "1_1") (pintype "passive"))
      (node (ref "R43") (pin "2") (pinfunction "2_2") (pintype "passive"))
    )
    (net (code "81") (name "Net-(IC10A--IN)") (class "Default")
      (node (ref "C29") (pin "1") (pinfunction "1_1") (pintype "passive"))
      (node (ref "IC10") (pin "2") (pinfunction "-IN_2") (pintype "input"))
      (node (ref "R50") (pin "1") (pinfunction "1_1") (pintype "passive"))
      (node (ref "R56") (pin "2") (pinfunction "2_2") (pintype "passive"))
    )
    (net (code "82") (name "Net-(IC10A-OUT)") (class "Default")
      (node (ref "C29") (pin "2") (pinfunction "2_2") (pintype "passive"))
      (node (ref "IC10") (pin "1") (pinfunction "OUT_1") (pintype "output"))
      (node (ref "R55") (pin "2") (pinfunction "2_2") (pintype "passive"))
    )
    (net (code "83") (name "Net-(IC10B-+IN)") (class "Default")
      (node (ref "C22") (pin "1") (pinfunction "1_1") (pintype "passive"))
      (node (ref "IC10") (pin "5") (pinfunction "+IN_5") (pintype "input"))
      (node (ref "R46") (pin "1") (pinfunction "1_1") (pintype "passive"))
    )
    (net (code "84") (name "Net-(IC10B--IN)") (class "Default")
      (node (ref "C21") (pin "2") (pinfunction "2_2") (pintype "passive"))
      (node (ref "C24") (pin "+") (pinfunction "+_+") (pintype "passive"))
      (node (ref "IC10") (pin "6") (pinfunction "-IN_6") (pintype "input"))
      (node (ref "IC10") (pin "7") (pinfunction "OUT_7") (pintype "output"))
    )
    (net (code "85") (name "Net-(J1-3)") (class "Default")
      (node (ref "J1") (pin "P3") (pinfunction "3_P3") (pintype "passive"))
      (node (ref "R29") (pin "1") (pinfunction "1_1") (pintype "passive"))
    )
    (net (code "86") (name "Net-(J2-3)") (class "Default")
      (node (ref "J2") (pin "P3") (pinfunction "3_P3") (pintype "passive"))
      (node (ref "R54") (pin "1") (pinfunction "1_1") (pintype "passive"))
    )
    (net (code "87") (name "Net-(J3-3)") (class "Default")
      (node (ref "J3") (pin "P3") (pinfunction "3_P3") (pintype "passive"))
      (node (ref "R24") (pin "1") (pinfunction "1_1") (pintype "passive"))
    )
    (net (code "88") (name "Net-(J4-3)") (class "Default")
      (node (ref "J4") (pin "P3") (pinfunction "3_P3") (pintype "passive"))
      (node (ref "R48") (pin "1") (pinfunction "1_1") (pintype "passive"))
    )
    (net (code "89") (name "Net-(J5-3)") (class "Default")
      (node (ref "J5") (pin "P3") (pinfunction "3_P3") (pintype "passive"))
      (node (ref "R47") (pin "1") (pinfunction "1_1") (pintype "passive"))
    )
    (net (code "90") (name "Net-(J6-3)") (class "Default")
      (node (ref "J6") (pin "P3") (pinfunction "3_P3") (pintype "passive"))
      (node (ref "R55") (pin "1") (pinfunction "1_1") (pintype "passive"))
      (node (ref "R56") (pin "1") (pinfunction "1_1") (pintype "passive"))
    )
    (net (code "91") (name "Net-(Q1-PadB)") (class "Default")
      (node (ref "Q1") (pin "B") (pinfunction "B_B") (pintype "passive"))
      (node (ref "R1") (pin "2") (pinfunction "2_2") (pintype "passive"))
    )
    (net (code "92") (name "Net-(Q2-PadB)") (class "Default")
      (node (ref "Q2") (pin "B") (pinfunction "B_B") (pintype "passive"))
      (node (ref "R2") (pin "2") (pinfunction "2_2") (pintype "passive"))
    )
    (net (code "93") (name "Net-(Q3-PadB)") (class "Default")
      (node (ref "Q3") (pin "B") (pinfunction "B_B") (pintype "passive"))
      (node (ref "R3") (pin "2") (pinfunction "2_2") (pintype "passive"))
    )
    (net (code "94") (name "Net-(Q4-PadB)") (class "Default")
      (node (ref "Q4") (pin "B") (pinfunction "B_B") (pintype "passive"))
      (node (ref "R11") (pin "2") (pinfunction "2_2") (pintype "passive"))
    )
    (net (code "95") (name "Net-(Q6-PadB)") (class "Default")
      (node (ref "Q6") (pin "B") (pinfunction "B_B") (pintype "passive"))
      (node (ref "R29") (pin "2") (pinfunction "2_2") (pintype "passive"))
    )
    (net (code "96") (name "Net-(R20-S)") (class "Default")
      (node (ref "R20") (pin "P$2") (pinfunction "S_P$2") (pintype "passive"))
      (node (ref "R39") (pin "1") (pinfunction "1_1") (pintype "passive"))
    )
    (net (code "97") (name "Net-(R21-S)") (class "Default")
      (node (ref "R21") (pin "P$2") (pinfunction "S_P$2") (pintype "passive"))
      (node (ref "R24") (pin "2") (pinfunction "2_2") (pintype "passive"))
    )
    (net (code "98") (name "Net-(R36-S)") (class "Default")
      (node (ref "R28") (pin "1") (pinfunction "1_1") (pintype "passive"))
      (node (ref "R36") (pin "P$2") (pinfunction "S_P$2") (pintype "passive"))
    )
    (net (code "99") (name "Net-(R37-S)") (class "Default")
      (node (ref "R37") (pin "P$2") (pinfunction "S_P$2") (pintype "passive"))
      (node (ref "R48") (pin "2") (pinfunction "2_2") (pintype "passive"))
    )
    (net (code "100") (name "Net-(R38-S)") (class "Default")
      (node (ref "R32") (pin "1") (pinfunction "1_1") (pintype "passive"))
      (node (ref "R38") (pin "P$2") (pinfunction "S_P$2") (pintype "passive"))
    )
    (net (code "101") (name "Net-(SJA-Pad2)") (class "Default")
      (node (ref "SJA") (pin "2") (pinfunction "2_2") (pintype "passive"))
      (node (ref "SW1") (pin "B") (pinfunction "B_B") (pintype "passive"))
    )
    (net (code "102") (name "Net-(SJB-Pad2)") (class "Default")
      (node (ref "SJB") (pin "2") (pinfunction "2_2") (pintype "passive"))
      (node (ref "SW1") (pin "A") (pinfunction "A_A") (pintype "passive"))
    )
    (net (code "103") (name "Net-(UC1-PD0-OSC_IN)") (class "Default")
      (node (ref "C9") (pin "2") (pinfunction "2_2") (pintype "passive"))
      (node (ref "Q5") (pin "2") (pinfunction "2_2") (pintype "passive"))
      (node (ref "UC1") (pin "5") (pinfunction "PD0-OSC_IN_5") (pintype "input"))
    )
    (net (code "104") (name "Net-(UC1-PD1-OSC_OUT)") (class "Default")
      (node (ref "C10") (pin "2") (pinfunction "2_2") (pintype "passive"))
      (node (ref "Q5") (pin "1") (pinfunction "1_1") (pintype "passive"))
      (node (ref "UC1") (pin "6") (pinfunction "PD1-OSC_OUT_6") (pintype "input"))
    )
    (net (code "105") (name "PARAM1_CV") (class "Default")
      (node (ref "C13") (pin "2") (pinfunction "2_2") (pintype "passive"))
      (node (ref "IC4") (pin "1") (pinfunction "CH0_1") (pintype "bidirectional"))
      (node (ref "IC7") (pin "14") (pinfunction "OUT_14") (pintype "output"))
      (node (ref "R25") (pin "2") (pinfunction "2_2") (pintype "passive"))
    )
    (net (code "106") (name "PARAM2_CV") (class "Default")
      (node (ref "C14") (pin "2") (pinfunction "2_2") (pintype "passive"))
      (node (ref "IC4") (pin "2") (pinfunction "CH1_2") (pintype "bidirectional"))
      (node (ref "IC7") (pin "8") (pinfunction "OUT_8") (pintype "output"))
      (node (ref "R26") (pin "2") (pinfunction "2_2") (pintype "passive"))
    )
    (net (code "107") (name "PITCH_CV") (class "Default")
      (node (ref "C16") (pin "2") (pinfunction "2_2") (pintype "passive"))
      (node (ref "IC4") (pin "3") (pinfunction "CH2_3") (pintype "bidirectional"))
      (node (ref "IC7") (pin "1") (pinfunction "OUT_1") (pintype "output"))
      (node (ref "R34") (pin "2") (pinfunction "2_2") (pintype "passive"))
    )
    (net (code "108") (name "RESET") (class "Default")
      (node (ref "JP2") (pin "10") (pinfunction "10_10") (pintype "passive"))
      (node (ref "JP4") (pin "2") (pinfunction "2_2") (pintype "passive"))
      (node (ref "R22") (pin "1") (pinfunction "1_1") (pintype "passive"))
      (node (ref "SW2") (pin "B") (pinfunction "S_B") (pintype "passive"))
      (node (ref "SW2") (pin "B'") (pinfunction "S1_B'") (pintype "passive"))
      (node (ref "UC1") (pin "7") (pinfunction "NRST_7") (pintype "input"))
    )
    (net (code "109") (name "RX") (class "Default")
      (node (ref "JP3") (pin "4") (pinfunction "4_4") (pintype "passive"))
      (node (ref "JP4") (pin "6") (pinfunction "6_6") (pintype "passive"))
      (node (ref "UC1") (pin "31") (pinfunction "PA10/USART1_RX/TIM1_CH3_31") (pintype "bidirectional"))
    )
    (net (code "110") (name "TX") (class "Default")
      (node (ref "JP3") (pin "5") (pinfunction "5_5") (pintype "passive"))
      (node (ref "JP4") (pin "4") (pinfunction "4_4") (pintype "passive"))
      (node (ref "UC1") (pin "30") (pinfunction "PA9/USART1_TX/TIM1_CH2_30") (pintype "input"))
    )
    (net (code "111") (name "VCC") (class "Default")
      (node (ref "C23") (pin "1") (pinfunction "1_1") (pintype "passive"))
      (node (ref "C25") (pin "+") (pinfunction "+_+") (pintype "passive"))
      (node (ref "C28") (pin "1") (pinfunction "1_1") (pintype "passive"))
      (node (ref "D1") (pin "C") (pinfunction "C_C") (pintype "passive"))
      (node (ref "IC10") (pin "8") (pinfunction "V+_8") (pintype "power_in"))
      (node (ref "IC9") (pin "4") (pinfunction "V+_4") (pintype "power_in"))
      (node (ref "R49") (pin "2") (pinfunction "2_2") (pintype "passive"))
    )
    (net (code "112") (name "VEE") (class "Default")
      (node (ref "C20") (pin "2") (pinfunction "2_2") (pintype "passive"))
      (node (ref "C27") (pin "2") (pinfunction "2_2") (pintype "passive"))
      (node (ref "C30") (pin "-") (pinfunction "-_-") (pintype "passive"))
      (node (ref "D2") (pin "A") (pinfunction "A_A") (pintype "passive"))
      (node (ref "IC10") (pin "4") (pinfunction "V-_4") (pintype "power_in"))
      (node (ref "IC9") (pin "11") (pinfunction "V-_11") (pintype "power_in"))
      (node (ref "R51") (pin "1") (pinfunction "1_1") (pintype "passive"))
    )
    (net (code "113") (name "unconnected-(DISP1-DP-Pad8)") (class "Default")
      (node (ref "DISP1") (pin "8") (pinfunction "DP_8") (pintype "passive"))
    )
    (net (code "114") (name "unconnected-(DISP2-DP-Pad8)") (class "Default")
      (node (ref "DISP2") (pin "8") (pinfunction "DP_8") (pintype "passive"))
    )
    (net (code "115") (name "unconnected-(IC1A-QG-Pad6)") (class "Default")
      (node (ref "IC1") (pin "6") (pinfunction "QG_6") (pintype "tri_state"))
    )
    (net (code "116") (name "unconnected-(IC1A-QH*-Pad9)") (class "Default")
      (node (ref "IC1") (pin "9") (pinfunction "QH*_9") (pintype "tri_state"))
    )
    (net (code "117") (name "unconnected-(IC1A-QH-Pad7)") (class "Default")
      (node (ref "IC1") (pin "7") (pinfunction "QH_7") (pintype "tri_state"))
    )
    (net (code "118") (name "unconnected-(J1-2-PadP2)") (class "Default")
      (node (ref "J1") (pin "P2") (pinfunction "2_P2") (pintype "passive"))
    )
    (net (code "119") (name "unconnected-(J2-2-PadP2)") (class "Default")
      (node (ref "J2") (pin "P2") (pinfunction "2_P2") (pintype "passive"))
    )
    (net (code "120") (name "unconnected-(J3-2-PadP2)") (class "Default")
      (node (ref "J3") (pin "P2") (pinfunction "2_P2") (pintype "passive"))
    )
    (net (code "121") (name "unconnected-(J4-2-PadP2)") (class "Default")
      (node (ref "J4") (pin "P2") (pinfunction "2_P2") (pintype "passive"))
    )
    (net (code "122") (name "unconnected-(J5-2-PadP2)") (class "Default")
      (node (ref "J5") (pin "P2") (pinfunction "2_P2") (pintype "passive"))
    )
    (net (code "123") (name "unconnected-(J6-2-PadP2)") (class "Default")
      (node (ref "J6") (pin "P2") (pinfunction "2_P2") (pintype "passive"))
    )
    (net (code "124") (name "unconnected-(JP2-Pad7)") (class "Default")
      (node (ref "JP2") (pin "7") (pinfunction "7_7") (pintype "passive"))
    )
    (net (code "125") (name "unconnected-(JP3-Pad2)") (class "Default")
      (node (ref "JP3") (pin "2") (pinfunction "2_2") (pintype "passive"))
    )
    (net (code "126") (name "unconnected-(JP3-Pad3)") (class "Default")
      (node (ref "JP3") (pin "3") (pinfunction "3_3") (pintype "passive"))
    )
    (net (code "127") (name "unconnected-(JP3-Pad6)") (class "Default")
      (node (ref "JP3") (pin "6") (pinfunction "6_6") (pintype "passive"))
    )
    (net (code "128") (name "unconnected-(UC1-PA0_WKUP{slash}USART2_CTS{slash}ADC12_IN0{slash}TIM2_CH1_ETR-Pad10)") (class "Default")
      (node (ref "UC1") (pin "10") (pinfunction "PA0_WKUP/USART2_CTS/ADC12_IN0/TIM2_CH1_ETR_10") (pintype "bidirectional"))
    )
    (net (code "129") (name "unconnected-(UC1-PA1{slash}USART2_RTS{slash}ADC12_IN1{slash}TIM2_CH2-Pad11)") (class "Default")
      (node (ref "UC1") (pin "11") (pinfunction "PA1/USART2_RTS/ADC12_IN1/TIM2_CH2_11") (pintype "bidirectional"))
    )
    (net (code "130") (name "unconnected-(UC1-PA2{slash}USART2_TX{slash}ADC12_IN2{slash}TIM2_CH3-Pad12)") (class "Default")
      (node (ref "UC1") (pin "12") (pinfunction "PA2/USART2_TX/ADC12_IN2/TIM2_CH3_12") (pintype "bidirectional"))
    )
    (net (code "131") (name "unconnected-(UC1-PA8{slash}USART1_CK{slash}TIM1_CH1{slash}MCO-Pad29)") (class "Default")
      (node (ref "UC1") (pin "29") (pinfunction "PA8/USART1_CK/TIM1_CH1/MCO_29") (pintype "bidirectional"))
    )
    (net (code "132") (name "unconnected-(UC1-PA11{slash}USART1_CTS{slash}CAN_RX{slash}TIM1_CH4{slash}USBDM-Pad32)") (class "Default")
      (node (ref "UC1") (pin "32") (pinfunction "PA11/USART1_CTS/CAN_RX/TIM1_CH4/USBDM_32") (pintype "bidirectional"))
    )
    (net (code "133") (name "unconnected-(UC1-PA12{slash}USART1_RTS{slash}CAN_TX{slash}TIM1_ETR{slash}USBDP-Pad33)") (class "Default")
      (node (ref "UC1") (pin "33") (pinfunction "PA12/USART1_RTS/CAN_TX/TIM1_ETR/USBDP_33") (pintype "bidirectional"))
    )
    (net (code "134") (name "unconnected-(UC1-PB4{slash}NJTRST-Pad40)") (class "Default")
      (node (ref "UC1") (pin "40") (pinfunction "PB4/NJTRST_40") (pintype "bidirectional"))
    )
    (net (code "135") (name "unconnected-(UC1-PB14{slash}SPI2_MISO{slash}USART3_RTS{slash}TIM1_CH2N-Pad27)") (class "Default")
      (node (ref "UC1") (pin "27") (pinfunction "PB14/SPI2_MISO/USART3_RTS/TIM1_CH2N_27") (pintype "input"))
    )
  )
)
